# Microcontroller.net
KiCad netlist of a schematic drawn in Altium Designer
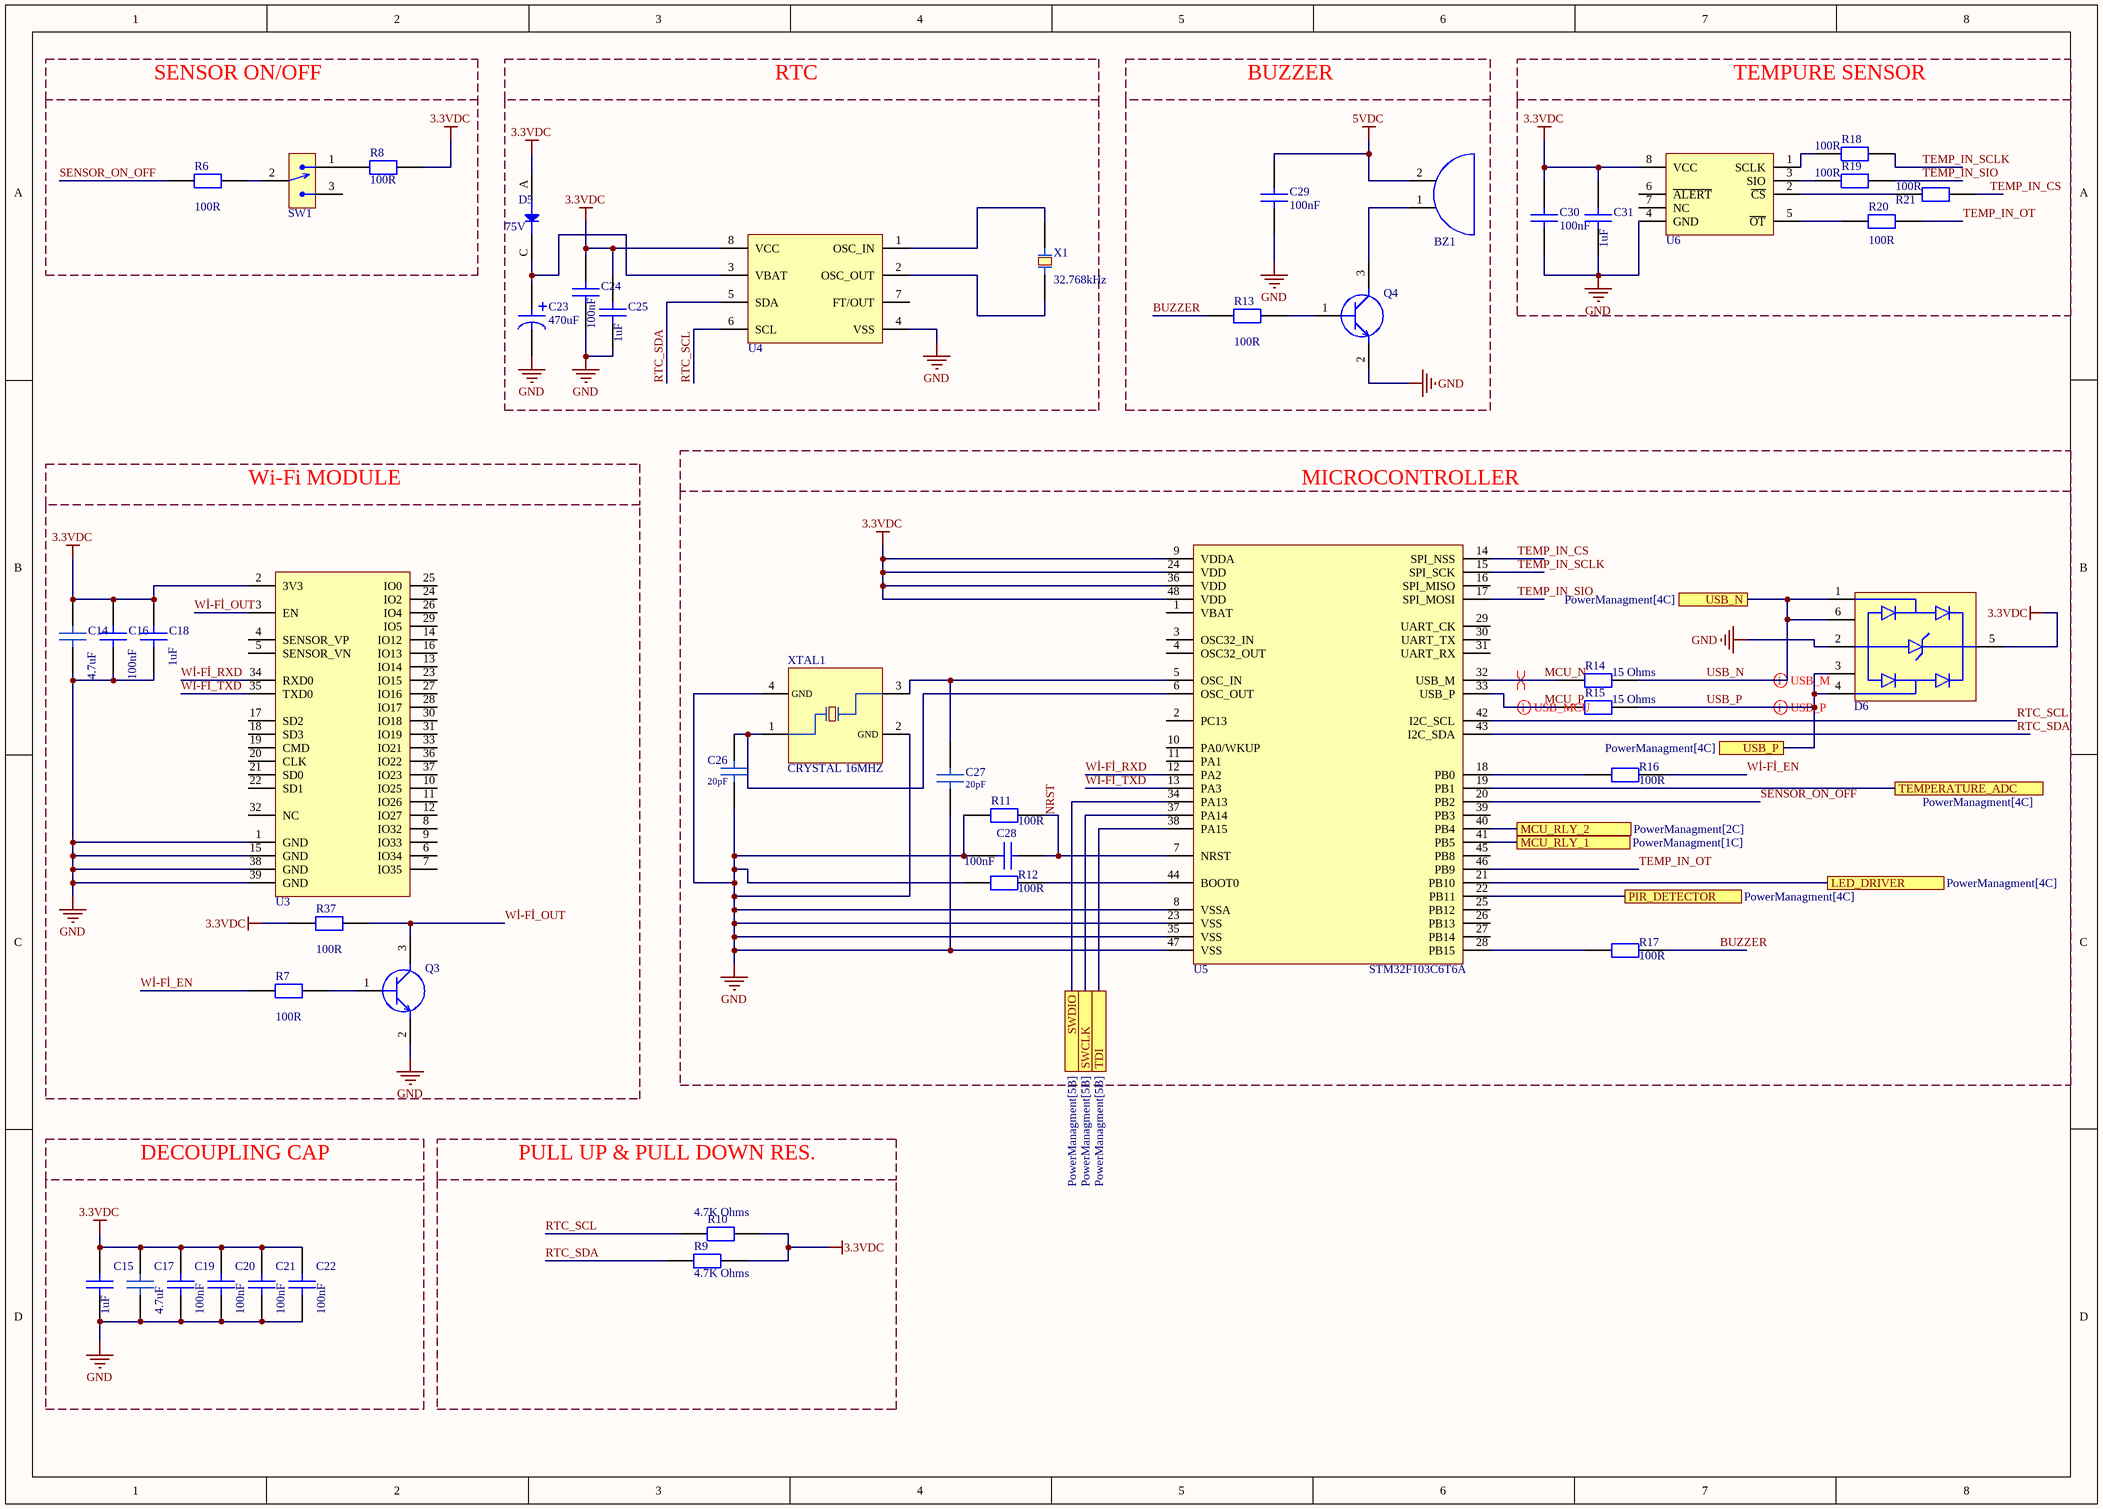
[diagram p0: Microcontroller.SchDoc]

(export (version "E")
  (design (tool "Eeschema 10.0.6"))
  (components
    (comp (ref "BZ1")
      (value "CMI-9605-0580T")
      (footprint "BUZZER CMI-9605-0580T")
      (description "9.6 mm, 5 Vdc, 80 dB, Through Hole, Driving Circuit, Magnetic Audio Indicator Buzzer")
      (fields (field (name "MANUFACTURER") "CUI Devices") (field (name "DESIGNED BY") "Görkem Bulut"))
      (libsource (lib "ComplexCurcuit") (part "CMI-9605-0580T"))
    )
    (comp (ref "C14")
      (value "4.7uF")
      (footprint "CAP 0805")
      (description "CAP CER 4.7UF 25V X5R 0805")
      (fields
        (field (name "MANUFACTURER") "Samsung")
        (field (name "MANUFACTURER PART NUMBER") "CL21A475KAQNNNE")
      )
      (libsource (lib "ComplexCurcuit") (part "CAP CER 4.7uF"))
    )
    (comp (ref "C15")
      (value "CAP CER 1UF 50V X7R 0805")
      (footprint "CAP 0805")
      (fields
        (field (name "MANUFACTURER") "Samsung")
        (field (name "MANUFACTURER PART NUMBER") "CL21B105KBFNNNE")
        (field (name "CAPACITANCE") "1uF")
        (field (name "DESIGNED BY") "Görkem Bulut")
      )
      (libsource (lib "ComplexCurcuit") (part "CAP CER 1uF"))
    )
    (comp (ref "C16")
      (value "CAP CER 100nF")
      (footprint "CAP 0603")
      (description "Cap Cer 0.1UF 16V X7R 0603 %10")
      (fields
        (field (name "MANUFACTURER") "KEMET")
        (field (name "MANUFACTURER PART NUMBER") "C0603C104K4RAC7082")
        (field (name "CAPACITANCE") "100nF")
        (field (name "DESIGNED BY") "Görkem Bulut")
      )
      (libsource (lib "ComplexCurcuit") (part "CAP CER 100nF"))
    )
    (comp (ref "C17")
      (value "4.7uF")
      (footprint "CAP 0805")
      (description "CAP CER 4.7UF 25V X5R 0805")
      (fields
        (field (name "MANUFACTURER") "Samsung")
        (field (name "MANUFACTURER PART NUMBER") "CL21A475KAQNNNE")
      )
      (libsource (lib "ComplexCurcuit") (part "CAP CER 4.7uF"))
    )
    (comp (ref "C18")
      (value "CAP CER 1UF 50V X7R 0805")
      (footprint "CAP 0805")
      (fields
        (field (name "MANUFACTURER") "Samsung")
        (field (name "MANUFACTURER PART NUMBER") "CL21B105KBFNNNE")
        (field (name "CAPACITANCE") "1uF")
        (field (name "DESIGNED BY") "Görkem Bulut")
      )
      (libsource (lib "ComplexCurcuit") (part "CAP CER 1uF"))
    )
    (comp (ref "C19")
      (value "CAP CER 100nF")
      (footprint "CAP 0603")
      (description "Cap Cer 0.1UF 16V X7R 0603 %10")
      (fields
        (field (name "MANUFACTURER") "KEMET")
        (field (name "MANUFACTURER PART NUMBER") "C0603C104K4RAC7082")
        (field (name "CAPACITANCE") "100nF")
        (field (name "DESIGNED BY") "Görkem Bulut")
      )
      (libsource (lib "ComplexCurcuit") (part "CAP CER 100nF"))
    )
    (comp (ref "C20")
      (value "CAP CER 100nF")
      (footprint "CAP 0603")
      (description "Cap Cer 0.1UF 16V X7R 0603 %10")
      (fields
        (field (name "MANUFACTURER") "KEMET")
        (field (name "MANUFACTURER PART NUMBER") "C0603C104K4RAC7082")
        (field (name "CAPACITANCE") "100nF")
        (field (name "DESIGNED BY") "Görkem Bulut")
      )
      (libsource (lib "ComplexCurcuit") (part "CAP CER 100nF"))
    )
    (comp (ref "C21")
      (value "CAP CER 100nF")
      (footprint "CAP 0603")
      (description "Cap Cer 0.1UF 16V X7R 0603 %10")
      (fields
        (field (name "MANUFACTURER") "KEMET")
        (field (name "MANUFACTURER PART NUMBER") "C0603C104K4RAC7082")
        (field (name "CAPACITANCE") "100nF")
        (field (name "DESIGNED BY") "Görkem Bulut")
      )
      (libsource (lib "ComplexCurcuit") (part "CAP CER 100nF"))
    )
    (comp (ref "C22")
      (value "CAP CER 100nF")
      (footprint "CAP 0603")
      (description "Cap Cer 0.1UF 16V X7R 0603 %10")
      (fields
        (field (name "MANUFACTURER") "KEMET")
        (field (name "MANUFACTURER PART NUMBER") "C0603C104K4RAC7082")
        (field (name "CAPACITANCE") "100nF")
        (field (name "DESIGNED BY") "Görkem Bulut")
      )
      (libsource (lib "ComplexCurcuit") (part "CAP CER 100nF"))
    )
    (comp (ref "C23")
      (value "ESH477M050AH4AA CAP")
      (footprint "CAP _RADİAL_D10_P5")
      (description "Cap, 470UF, 50V, Alu Elec, Radial")
      (fields
        (field (name "MANUFACTURER") "KEMET")
        (field (name "MANUFACTURER PART NUMBER") "ESH477M050AH4AA")
        (field (name "CAPACITANCE") "470uF")
        (field (name "DESIGNED BY") "Görkem Bulut")
      )
      (libsource (lib "ComplexCurcuit") (part "ESH477M050AH4AA CAP"))
    )
    (comp (ref "C24")
      (value "100nF")
      (footprint "CAP 0805")
      (description "Multilayer Ceramic Capacitor, 0.1 uF, 50 V, ± 10%, X7R, 0805 [2012 Metric]")
      (fields
        (field (name "MANUFACTURER") "Samsung")
        (field (name "MANUFACTURER PART NUMBER") "CL21B104KBCNNNC")
      )
      (libsource (lib "ComplexCurcuit") (part "CAP CER 100nF 0805"))
    )
    (comp (ref "C25")
      (value "CAP CER 1UF 50V X7R 0805")
      (footprint "CAP 0805")
      (fields
        (field (name "MANUFACTURER") "Samsung")
        (field (name "MANUFACTURER PART NUMBER") "CL21B105KBFNNNE")
        (field (name "CAPACITANCE") "1uF")
        (field (name "DESIGNED BY") "Görkem Bulut")
      )
      (libsource (lib "ComplexCurcuit") (part "CAP CER 1uF"))
    )
    (comp (ref "C26")
      (value "CAP CER 20PF 50V C0G/NP0 0603")
      (footprint "CAP 0603")
      (fields
        (field (name "MANUFACTURER") "Samsung")
        (field (name "MANUFACTURER PART NUMBER") "CL10C200JB8NNNC")
        (field (name "CAPACITANCE") "20pF")
      )
      (libsource (lib "ComplexCurcuit") (part "CAP CER 20pF"))
    )
    (comp (ref "C27")
      (value "CAP CER 20PF 50V C0G/NP0 0603")
      (footprint "CAP 0603")
      (fields
        (field (name "MANUFACTURER") "Samsung")
        (field (name "MANUFACTURER PART NUMBER") "CL10C200JB8NNNC")
        (field (name "CAPACITANCE") "20pF")
      )
      (libsource (lib "ComplexCurcuit") (part "CAP CER 20pF"))
    )
    (comp (ref "C28")
      (value "CAP CER 100nF")
      (footprint "CAP 0603")
      (description "Cap Cer 0.1UF 16V X7R 0603 %10")
      (fields
        (field (name "MANUFACTURER") "KEMET")
        (field (name "MANUFACTURER PART NUMBER") "C0603C104K4RAC7082")
        (field (name "CAPACITANCE") "100nF")
        (field (name "DESIGNED BY") "Görkem Bulut")
      )
      (libsource (lib "ComplexCurcuit") (part "CAP CER 100nF"))
    )
    (comp (ref "C29")
      (value "100nF")
      (footprint "CAP 0805")
      (description "Multilayer Ceramic Capacitor, 0.1 uF, 50 V, ± 10%, X7R, 0805 [2012 Metric]")
      (fields
        (field (name "MANUFACTURER") "Samsung")
        (field (name "MANUFACTURER PART NUMBER") "CL21B104KBCNNNC")
      )
      (libsource (lib "ComplexCurcuit") (part "CAP CER 100nF 0805"))
    )
    (comp (ref "C30")
      (value "CAP CER 100nF")
      (footprint "CAP 0603")
      (description "Cap Cer 0.1UF 16V X7R 0603 %10")
      (fields
        (field (name "MANUFACTURER") "KEMET")
        (field (name "MANUFACTURER PART NUMBER") "C0603C104K4RAC7082")
        (field (name "CAPACITANCE") "100nF")
        (field (name "DESIGNED BY") "Görkem Bulut")
      )
      (libsource (lib "ComplexCurcuit") (part "CAP CER 100nF"))
    )
    (comp (ref "C31")
      (value "CAP CER 1UF 50V X7R 0805")
      (footprint "CAP 0805")
      (fields
        (field (name "MANUFACTURER") "Samsung")
        (field (name "MANUFACTURER PART NUMBER") "CL21B105KBFNNNE")
        (field (name "CAPACITANCE") "1uF")
        (field (name "DESIGNED BY") "Görkem Bulut")
      )
      (libsource (lib "ComplexCurcuit") (part "CAP CER 1uF"))
    )
    (comp (ref "D5")
      (value "DIODE GEN PURP 75V 150MA SOD323F")
      (footprint "SOD323F")
      (description "VR=75V IF=150mA Trr=4ns P=200mW")
      (fields
        (field (name "MANUFACTURER") "ON Semiconductor / Fairchild")
        (field (name "MANUFACTURER PART NUMBER") "1N4148WS")
        (field (name "OPERATING VOLTAGE") "75V")
        (field (name "DESIGNED BY") "Görkem Bulut")
      )
      (libsource (lib "ComplexCurcuit") (part "1N4148WS"))
    )
    (comp (ref "D6")
      (value "TVS DIODE 5.25VWM 17VC SOT23-6")
      (footprint "SOT23-6L")
      (fields
        (field (name "MANUFACTURER") "STMicroelectronics")
        (field (name "MANUFACTURER PART NUMBER") "USBLC6-2SC6")
        (field (name "DESIGNED BY") "Görkem Bulut")
      )
      (libsource (lib "ComplexCurcuit") (part "USBLC6-2SC6"))
    )
    (comp (ref "Q3")
      (value "MMBT3904-7-F")
      (footprint "SOT23F")
      (description "Transistor General Purpose BJT NPN 40 Volt 0.2A Automotive 3-Pin SOT-23")
      (fields (field (name "MANUFACTURER") "Diodes Zetex") (field (name "DESIGNED BY") "Gökem Bulut"))
      (libsource (lib "ComplexCurcuit") (part "MMBT3904-7-F"))
    )
    (comp (ref "Q4")
      (value "MMBT3904-7-F")
      (footprint "SOT23F")
      (description "Transistor General Purpose BJT NPN 40 Volt 0.2A Automotive 3-Pin SOT-23")
      (fields (field (name "MANUFACTURER") "Diodes Zetex") (field (name "DESIGNED BY") "Gökem Bulut"))
      (libsource (lib "ComplexCurcuit") (part "MMBT3904-7-F"))
    )
    (comp (ref "R6")
      (value "RC0603JR-07100RL")
      (footprint "RES 0603")
      (description "Res Thick Film 0603 100 Ohm 5% 1/10W ±100ppm/°C Molded SMD SMD Paper T/R")
      (fields
        (field (name "MANUFACTURER") "Yageo")
        (field (name "TOLERANCE") "5%")
        (field (name "RESISTANCE") "100R")
        (field (name "DESIGNED BY") "G.B")
      )
      (libsource (lib "ComplexCurcuit") (part "RES 100 OHM"))
    )
    (comp (ref "R7")
      (value "RC0603JR-07100RL")
      (footprint "RES 0603")
      (description "Res Thick Film 0603 100 Ohm 5% 1/10W ±100ppm/°C Molded SMD SMD Paper T/R")
      (fields
        (field (name "MANUFACTURER") "Yageo")
        (field (name "TOLERANCE") "5%")
        (field (name "RESISTANCE") "100R")
        (field (name "DESIGNED BY") "G.B")
      )
      (libsource (lib "ComplexCurcuit") (part "RES 100 OHM"))
    )
    (comp (ref "R8")
      (value "RC0603JR-07100RL")
      (footprint "RES 0603")
      (description "Res Thick Film 0603 100 Ohm 5% 1/10W ±100ppm/°C Molded SMD SMD Paper T/R")
      (fields
        (field (name "MANUFACTURER") "Yageo")
        (field (name "TOLERANCE") "5%")
        (field (name "RESISTANCE") "100R")
        (field (name "DESIGNED BY") "G.B")
      )
      (libsource (lib "ComplexCurcuit") (part "RES 100 OHM"))
    )
    (comp (ref "R9")
      (value "RC0603JR-074K7L")
      (footprint "RES 0603")
      (description "Res General Purpose Thick Film 0603 4.7k Ohm 5% 1/10W ±100ppm/°C Molded Paper T/R")
      (fields
        (field (name "MANUFACTURER") "Yageo")
        (field (name "RESISTANCE") "4.7K Ohms")
        (field (name "DESIGNED BY") "Görkem Bulut")
      )
      (libsource (lib "ComplexCurcuit") (part "RES 4K7 OHM"))
    )
    (comp (ref "R10")
      (value "RC0603JR-074K7L")
      (footprint "RES 0603")
      (description "Res General Purpose Thick Film 0603 4.7k Ohm 5% 1/10W ±100ppm/°C Molded Paper T/R")
      (fields
        (field (name "MANUFACTURER") "Yageo")
        (field (name "RESISTANCE") "4.7K Ohms")
        (field (name "DESIGNED BY") "Görkem Bulut")
      )
      (libsource (lib "ComplexCurcuit") (part "RES 4K7 OHM"))
    )
    (comp (ref "R11")
      (value "RC0603JR-07100RL")
      (footprint "RES 0603")
      (description "Res Thick Film 0603 100 Ohm 5% 1/10W ±100ppm/°C Molded SMD SMD Paper T/R")
      (fields
        (field (name "MANUFACTURER") "Yageo")
        (field (name "TOLERANCE") "5%")
        (field (name "RESISTANCE") "100R")
        (field (name "DESIGNED BY") "G.B")
      )
      (libsource (lib "ComplexCurcuit") (part "RES 100 OHM"))
    )
    (comp (ref "R12")
      (value "RC0603JR-07100RL")
      (footprint "RES 0603")
      (description "Res Thick Film 0603 100 Ohm 5% 1/10W ±100ppm/°C Molded SMD SMD Paper T/R")
      (fields
        (field (name "MANUFACTURER") "Yageo")
        (field (name "TOLERANCE") "5%")
        (field (name "RESISTANCE") "100R")
        (field (name "DESIGNED BY") "G.B")
      )
      (libsource (lib "ComplexCurcuit") (part "RES 100 OHM"))
    )
    (comp (ref "R13")
      (value "RC0603JR-07100RL")
      (footprint "RES 0603")
      (description "Res Thick Film 0603 100 Ohm 5% 1/10W ±100ppm/°C Molded SMD SMD Paper T/R")
      (fields
        (field (name "MANUFACTURER") "Yageo")
        (field (name "TOLERANCE") "5%")
        (field (name "RESISTANCE") "100R")
        (field (name "DESIGNED BY") "G.B")
      )
      (libsource (lib "ComplexCurcuit") (part "RES 100 OHM"))
    )
    (comp (ref "R14")
      (value "RC0603JR-0715RL")
      (footprint "RES 0603")
      (description "Res Thick Film 0603 15 Ohm 5% 0.1W(1/10W) ±100ppm/C Pad SMD T/R")
      (fields
        (field (name "MANUFACTURER") "Yageo")
        (field (name "RESISTANCE") "15 Ohms")
        (field (name "DESIGNED BY") "Görkem Bulut")
      )
      (libsource (lib "ComplexCurcuit") (part "RES 15 OHM"))
    )
    (comp (ref "R15")
      (value "RC0603JR-0715RL")
      (footprint "RES 0603")
      (description "Res Thick Film 0603 15 Ohm 5% 0.1W(1/10W) ±100ppm/C Pad SMD T/R")
      (fields
        (field (name "MANUFACTURER") "Yageo")
        (field (name "RESISTANCE") "15 Ohms")
        (field (name "DESIGNED BY") "Görkem Bulut")
      )
      (libsource (lib "ComplexCurcuit") (part "RES 15 OHM"))
    )
    (comp (ref "R16")
      (value "RC0603JR-07100RL")
      (footprint "RES 0603")
      (description "Res Thick Film 0603 100 Ohm 5% 1/10W ±100ppm/°C Molded SMD SMD Paper T/R")
      (fields
        (field (name "MANUFACTURER") "Yageo")
        (field (name "TOLERANCE") "5%")
        (field (name "RESISTANCE") "100R")
        (field (name "DESIGNED BY") "G.B")
      )
      (libsource (lib "ComplexCurcuit") (part "RES 100 OHM"))
    )
    (comp (ref "R17")
      (value "RC0603JR-07100RL")
      (footprint "RES 0603")
      (description "Res Thick Film 0603 100 Ohm 5% 1/10W ±100ppm/°C Molded SMD SMD Paper T/R")
      (fields
        (field (name "MANUFACTURER") "Yageo")
        (field (name "TOLERANCE") "5%")
        (field (name "RESISTANCE") "100R")
        (field (name "DESIGNED BY") "G.B")
      )
      (libsource (lib "ComplexCurcuit") (part "RES 100 OHM"))
    )
    (comp (ref "R18")
      (value "RC0603JR-07100RL")
      (footprint "RES 0603")
      (description "Res Thick Film 0603 100 Ohm 5% 1/10W ±100ppm/°C Molded SMD SMD Paper T/R")
      (fields
        (field (name "MANUFACTURER") "Yageo")
        (field (name "TOLERANCE") "5%")
        (field (name "RESISTANCE") "100R")
        (field (name "DESIGNED BY") "G.B")
      )
      (libsource (lib "ComplexCurcuit") (part "RES 100 OHM"))
    )
    (comp (ref "R19")
      (value "RC0603JR-07100RL")
      (footprint "RES 0603")
      (description "Res Thick Film 0603 100 Ohm 5% 1/10W ±100ppm/°C Molded SMD SMD Paper T/R")
      (fields
        (field (name "MANUFACTURER") "Yageo")
        (field (name "TOLERANCE") "5%")
        (field (name "RESISTANCE") "100R")
        (field (name "DESIGNED BY") "G.B")
      )
      (libsource (lib "ComplexCurcuit") (part "RES 100 OHM"))
    )
    (comp (ref "R20")
      (value "RC0603JR-07100RL")
      (footprint "RES 0603")
      (description "Res Thick Film 0603 100 Ohm 5% 1/10W ±100ppm/°C Molded SMD SMD Paper T/R")
      (fields
        (field (name "MANUFACTURER") "Yageo")
        (field (name "TOLERANCE") "5%")
        (field (name "RESISTANCE") "100R")
        (field (name "DESIGNED BY") "G.B")
      )
      (libsource (lib "ComplexCurcuit") (part "RES 100 OHM"))
    )
    (comp (ref "R21")
      (value "RC0603JR-07100RL")
      (footprint "RES 0603")
      (description "Res Thick Film 0603 100 Ohm 5% 1/10W ±100ppm/°C Molded SMD SMD Paper T/R")
      (fields
        (field (name "MANUFACTURER") "Yageo")
        (field (name "TOLERANCE") "5%")
        (field (name "RESISTANCE") "100R")
        (field (name "DESIGNED BY") "G.B")
      )
      (libsource (lib "ComplexCurcuit") (part "RES 100 OHM"))
    )
    (comp (ref "R37")
      (value "RC0603JR-07100RL")
      (footprint "RES 0603")
      (description "Res Thick Film 0603 100 Ohm 5% 1/10W ±100ppm/°C Molded SMD SMD Paper T/R")
      (fields
        (field (name "MANUFACTURER") "Yageo")
        (field (name "TOLERANCE") "5%")
        (field (name "RESISTANCE") "100R")
        (field (name "DESIGNED BY") "G.B")
      )
      (libsource (lib "ComplexCurcuit") (part "RES 100 OHM"))
    )
    (comp (ref "SW1")
      (value "EG1215AA")
      (footprint "EG1215AA")
      (description "Slide Switch, SPDT, 0.025A, 24V, SMD")
      (fields (field (name "MANUFACTURER") "E-Switch") (field (name "DESIGNED BY") "Görkem Bulut"))
      (libsource (lib "ComplexCurcuit") (part "EG1215AA"))
    )
    (comp (ref "U3")
      (value "ESP32-VROOM-32")
      (footprint "ESP-32-32E")
      (fields
        (field (name "MANUFACTURER PART NUMBER") "ESP32-WROOM-32E(4MB)")
        (field (name "MANUFACTURER") "Espressif Systems")
        (field (name "DESIGNED BY") "Görkem Bulut")
      )
      (libsource (lib "ComplexCurcuit") (part "ESP32-VROOM-32"))
    )
    (comp (ref "U4")
      (value "M41T00M6F")
      (footprint "SOIC8")
      (description "Real-time Clocks Clock/Calendar I2C, 2-Wire Serial 70uA @ 2V ~ 5.5V SOIC-8_150mil RoHS")
      (fields (field (name "MANUFACTURER") "STMicroelectronics") (field (name "DESIGNED BY") "Görkem Bulut"))
      (libsource (lib "ComplexCurcuit") (part "M41T00M6F"))
    )
    (comp (ref "U5")
      (value "STM32F103C6T6A")
      (footprint "LQFP48")
      (description "MCU 32-bit STM32F ARM Cortex M3 RISC 32KB Flash 2.5V/3.3V 48-Pin LQFP Tray")
      (fields (field (name "MANUFACTURER") "STMicroelectronics") (field (name "DESIGNED BY") "Görkem BULUT"))
      (libsource (lib "ComplexCurcuit") (part "STM32F103C6T6A"))
    )
    (comp (ref "U6")
      (value "MAX6662MSA+")
      (footprint "SOIC8")
      (description "Temp Sensor Digital Serial (3-Wire, SPI) 8-Pin SOIC N Tube")
      (fields (field (name "MANUFACTURER") "Maxim") (field (name "DESIGNED BY") "Görkem Bulut"))
      (libsource (lib "ComplexCurcuit") (part "MAX6662MSA+"))
    )
    (comp (ref "X1")
      (value "CRYSTAL 32.7680KHZ 12.5PF SMD")
      (footprint "ABS05")
      (description "CRYSTAL 32.768kHz ±20ppm Crystal 12.5pF 90 kOhm -40°C ^ 85°C Surface Mount 2-SMD")
      (fields
        (field (name "MANUFACTURER") "Abracon")
        (field (name "MANUFACTURER PART NUMBER") "ABS05-32.768KHZ-T")
        (field (name "FREQUENCY") "32.768kHz")
      )
      (libsource (lib "ComplexCurcuit") (part "CRYSTAL OSC 32.768 kHz"))
    )
    (comp (ref "XTAL1")
      (value "CRYSTAL 16MHZ")
      (footprint "ECS-160-20-30B-TR")
      (description "Crystal 16MHz ±30ppm (Tol) ±50ppm (Stability) 20pF FUND 50Ohm 4-Pin Mini-SMD T/R")
      (fields
        (field (name "MANUFACTURER") "ECS International")
        (field (name "MANUFACTURER PART NUMBER") "ECS-160-20-30B-TR")
        (field (name "DESIGNED BY") "Görkem B.")
      )
      (libsource (lib "ComplexCurcuit") (part "CRYSTAL 16MHZ"))
    )
  )
  (nets
    (net (code "1") (name "/BUZZER") (class "Default")
      (node (ref "R13") (pin "1") (pinfunction "1_1") (pintype "passive"))
      (node (ref "R17") (pin "2") (pinfunction "2_2") (pintype "passive"))
    )
    (net (code "2") (name "/LED_DRIVER") (class "Default")
      (node (ref "U5") (pin "21") (pinfunction "PB10_21") (pintype "passive"))
    )
    (net (code "3") (name "/MCU_N") (class "Default")
      (node (ref "R14") (pin "2") (pinfunction "2_2") (pintype "passive"))
      (node (ref "U5") (pin "32") (pinfunction "_USB_M_32") (pintype "passive"))
    )
    (net (code "4") (name "/MCU_P") (class "Default")
      (node (ref "R15") (pin "2") (pinfunction "2_2") (pintype "passive"))
      (node (ref "U5") (pin "33") (pinfunction "_USB_P_33") (pintype "passive"))
    )
    (net (code "5") (name "/MCU_RLY_1") (class "Default")
      (node (ref "U5") (pin "41") (pinfunction "PB5_41") (pintype "passive"))
    )
    (net (code "6") (name "/MCU_RLY_2") (class "Default")
      (node (ref "U5") (pin "40") (pinfunction "PB4_40") (pintype "passive"))
    )
    (net (code "7") (name "/NRST") (class "Default")
      (node (ref "C28") (pin "2") (pinfunction "2_2") (pintype "passive"))
      (node (ref "R11") (pin "2") (pinfunction "2_2") (pintype "passive"))
      (node (ref "U5") (pin "7") (pinfunction "NRST_7") (pintype "passive"))
    )
    (net (code "8") (name "/PIR_DETECTOR") (class "Default")
      (node (ref "U5") (pin "22") (pinfunction "PB11_22") (pintype "passive"))
    )
    (net (code "9") (name "/RTC_SCL") (class "Default")
      (node (ref "R10") (pin "1") (pinfunction "1_1") (pintype "passive"))
      (node (ref "U4") (pin "6") (pinfunction "SCL_6") (pintype "passive"))
      (node (ref "U5") (pin "42") (pinfunction "I2C_SCL_42") (pintype "passive"))
    )
    (net (code "10") (name "/RTC_SDA") (class "Default")
      (node (ref "R9") (pin "1") (pinfunction "1_1") (pintype "passive"))
      (node (ref "U4") (pin "5") (pinfunction "SDA_5") (pintype "passive"))
      (node (ref "U5") (pin "43") (pinfunction "I2C_SDA_43") (pintype "passive"))
    )
    (net (code "11") (name "/SENSOR_ON_OFF") (class "Default")
      (node (ref "R6") (pin "1") (pinfunction "1_1") (pintype "passive"))
      (node (ref "U5") (pin "20") (pinfunction "PB2_20") (pintype "passive"))
    )
    (net (code "12") (name "/SWCLK") (class "Default")
      (node (ref "U5") (pin "37") (pinfunction "PA14_37") (pintype "passive"))
    )
    (net (code "13") (name "/SWDIO") (class "Default")
      (node (ref "U5") (pin "34") (pinfunction "PA13_34") (pintype "passive"))
    )
    (net (code "14") (name "/TDI") (class "Default")
      (node (ref "U5") (pin "38") (pinfunction "PA15_38") (pintype "passive"))
    )
    (net (code "15") (name "/TEMPERATURE_ADC") (class "Default")
      (node (ref "U5") (pin "19") (pinfunction "PB1_19") (pintype "passive"))
    )
    (net (code "16") (name "/TEMP_IN_CS") (class "Default")
      (node (ref "R21") (pin "2") (pinfunction "2_2") (pintype "passive"))
      (node (ref "U5") (pin "14") (pinfunction "SPI_NSS_14") (pintype "passive"))
    )
    (net (code "17") (name "/TEMP_IN_OT") (class "Default")
      (node (ref "R20") (pin "2") (pinfunction "2_2") (pintype "passive"))
      (node (ref "U5") (pin "46") (pinfunction "PB9_46") (pintype "passive"))
    )
    (net (code "18") (name "/TEMP_IN_SCLK") (class "Default")
      (node (ref "R18") (pin "2") (pinfunction "2_2") (pintype "passive"))
      (node (ref "U5") (pin "15") (pinfunction "SPI_SCK_15") (pintype "passive"))
    )
    (net (code "19") (name "/TEMP_IN_SIO") (class "Default")
      (node (ref "R19") (pin "2") (pinfunction "2_2") (pintype "passive"))
      (node (ref "U5") (pin "17") (pinfunction "SPI_MOSI_17") (pintype "passive"))
    )
    (net (code "20") (name "/USB_N") (class "Default")
      (node (ref "D6") (pin "1") (pinfunction "I/O1_1") (pintype "passive"))
      (node (ref "D6") (pin "6") (pinfunction "I/O1_6") (pintype "passive"))
      (node (ref "R14") (pin "1") (pinfunction "1_1") (pintype "passive"))
    )
    (net (code "21") (name "/USB_P") (class "Default")
      (node (ref "D6") (pin "3") (pinfunction "I/O2_3") (pintype "passive"))
      (node (ref "D6") (pin "4") (pinfunction "_I/O2_4") (pintype "passive"))
      (node (ref "R15") (pin "1") (pinfunction "1_1") (pintype "passive"))
    )
    (net (code "22") (name "/Wİ-Fİ_EN") (class "Default")
      (node (ref "R16") (pin "2") (pinfunction "2_2") (pintype "passive"))
      (node (ref "R7") (pin "1") (pinfunction "1_1") (pintype "passive"))
    )
    (net (code "23") (name "/Wİ-Fİ_OUT") (class "Default")
      (node (ref "Q3") (pin "3") (pinfunction "CONNECTOR_3") (pintype "passive"))
      (node (ref "R37") (pin "2") (pinfunction "2_2") (pintype "passive"))
      (node (ref "U3") (pin "3") (pinfunction "EN_3") (pintype "passive"))
    )
    (net (code "24") (name "/Wİ-Fİ_RXD") (class "Default")
      (node (ref "U3") (pin "34") (pinfunction "RXD0_34") (pintype "passive"))
      (node (ref "U5") (pin "12") (pinfunction "PA2_12") (pintype "passive"))
    )
    (net (code "25") (name "/Wİ-Fİ_TXD") (class "Default")
      (node (ref "U3") (pin "35") (pinfunction "TXD0_35") (pintype "passive"))
      (node (ref "U5") (pin "13") (pinfunction "PA3_13") (pintype "passive"))
    )
    (net (code "26") (name "3.3VDC") (class "Default")
      (node (ref "C14") (pin "2") (pinfunction "2_2") (pintype "passive"))
      (node (ref "C15") (pin "1") (pinfunction "1_1") (pintype "passive"))
      (node (ref "C16") (pin "2") (pinfunction "2_2") (pintype "passive"))
      (node (ref "C17") (pin "2") (pinfunction "2_2") (pintype "passive"))
      (node (ref "C18") (pin "1") (pinfunction "1_1") (pintype "passive"))
      (node (ref "C19") (pin "2") (pinfunction "2_2") (pintype "passive"))
      (node (ref "C20") (pin "2") (pinfunction "2_2") (pintype "passive"))
      (node (ref "C21") (pin "2") (pinfunction "2_2") (pintype "passive"))
      (node (ref "C22") (pin "2") (pinfunction "2_2") (pintype "passive"))
      (node (ref "C24") (pin "2") (pinfunction "2_2") (pintype "passive"))
      (node (ref "C25") (pin "1") (pinfunction "1_1") (pintype "passive"))
      (node (ref "C30") (pin "2") (pinfunction "2_2") (pintype "passive"))
      (node (ref "C31") (pin "1") (pinfunction "1_1") (pintype "passive"))
      (node (ref "D5") (pin "A") (pinfunction "Anode_A") (pintype "passive"))
      (node (ref "D6") (pin "5") (pinfunction "VBUS_5") (pintype "passive"))
      (node (ref "R10") (pin "2") (pinfunction "2_2") (pintype "passive"))
      (node (ref "R37") (pin "1") (pinfunction "1_1") (pintype "passive"))
      (node (ref "R8") (pin "2") (pinfunction "2_2") (pintype "passive"))
      (node (ref "R9") (pin "2") (pinfunction "2_2") (pintype "passive"))
      (node (ref "U3") (pin "2") (pinfunction "3V3_2") (pintype "passive"))
      (node (ref "U4") (pin "8") (pinfunction "VCC_8") (pintype "passive"))
      (node (ref "U5") (pin "24") (pinfunction "VDD_24") (pintype "passive"))
      (node (ref "U5") (pin "36") (pinfunction "VDD_36") (pintype "passive"))
      (node (ref "U5") (pin "48") (pinfunction "VDD_48") (pintype "passive"))
      (node (ref "U5") (pin "9") (pinfunction "VDDA_9") (pintype "passive"))
      (node (ref "U6") (pin "8") (pinfunction "VCC_8") (pintype "passive"))
    )
    (net (code "27") (name "5VDC") (class "Default")
      (node (ref "BZ1") (pin "2") (pinfunction "2_2") (pintype "passive"))
      (node (ref "C29") (pin "2") (pinfunction "2_2") (pintype "passive"))
    )
    (net (code "28") (name "GND") (class "Default")
      (node (ref "C14") (pin "1") (pinfunction "1_1") (pintype "passive"))
      (node (ref "C15") (pin "2") (pinfunction "2_2") (pintype "passive"))
      (node (ref "C16") (pin "1") (pinfunction "1_1") (pintype "passive"))
      (node (ref "C17") (pin "1") (pinfunction "1_1") (pintype "passive"))
      (node (ref "C18") (pin "2") (pinfunction "2_2") (pintype "passive"))
      (node (ref "C19") (pin "1") (pinfunction "1_1") (pintype "passive"))
      (node (ref "C20") (pin "1") (pinfunction "1_1") (pintype "passive"))
      (node (ref "C21") (pin "1") (pinfunction "1_1") (pintype "passive"))
      (node (ref "C22") (pin "1") (pinfunction "1_1") (pintype "passive"))
      (node (ref "C23") (pin "2") (pinfunction "2_2") (pintype "passive"))
      (node (ref "C24") (pin "1") (pinfunction "1_1") (pintype "passive"))
      (node (ref "C25") (pin "2") (pinfunction "2_2") (pintype "passive"))
      (node (ref "C26") (pin "1") (pinfunction "1_1") (pintype "passive"))
      (node (ref "C27") (pin "1") (pinfunction "1_1") (pintype "passive"))
      (node (ref "C28") (pin "1") (pinfunction "1_1") (pintype "passive"))
      (node (ref "C29") (pin "1") (pinfunction "1_1") (pintype "passive"))
      (node (ref "C30") (pin "1") (pinfunction "1_1") (pintype "passive"))
      (node (ref "C31") (pin "2") (pinfunction "2_2") (pintype "passive"))
      (node (ref "D6") (pin "2") (pinfunction "GND_2") (pintype "passive"))
      (node (ref "Q3") (pin "2") (pinfunction "EMİTTER_2") (pintype "passive"))
      (node (ref "Q4") (pin "2") (pinfunction "EMİTTER_2") (pintype "passive"))
      (node (ref "R11") (pin "1") (pinfunction "1_1") (pintype "passive"))
      (node (ref "R12") (pin "1") (pinfunction "1_1") (pintype "passive"))
      (node (ref "U3") (pin "1") (pinfunction "GND_1") (pintype "passive"))
      (node (ref "U3") (pin "15") (pinfunction "GND_15") (pintype "passive"))
      (node (ref "U3") (pin "38") (pinfunction "GND_38") (pintype "passive"))
      (node (ref "U3") (pin "39") (pinfunction "GND_39") (pintype "passive"))
      (node (ref "U4") (pin "4") (pinfunction "VSS_4") (pintype "passive"))
      (node (ref "U5") (pin "23") (pinfunction "VSS_23") (pintype "passive"))
      (node (ref "U5") (pin "35") (pinfunction "VSS_35") (pintype "passive"))
      (node (ref "U5") (pin "47") (pinfunction "VSS_47") (pintype "passive"))
      (node (ref "U5") (pin "8") (pinfunction "VSSA_8") (pintype "passive"))
      (node (ref "U6") (pin "4") (pinfunction "GND_4") (pintype "passive"))
      (node (ref "XTAL1") (pin "2") (pinfunction "GND_2") (pintype "passive"))
      (node (ref "XTAL1") (pin "4") (pinfunction "GND_4") (pintype "passive"))
    )
    (net (code "29") (name "Net-(D5-Cathode)") (class "Default")
      (node (ref "C23") (pin "1") (pinfunction "1_1") (pintype "passive"))
      (node (ref "D5") (pin "C") (pinfunction "Cathode_C") (pintype "passive"))
      (node (ref "U4") (pin "3") (pinfunction "VBAT_3") (pintype "passive"))
    )
    (net (code "30") (name "Net-(Q3-BASE)") (class "Default")
      (node (ref "Q3") (pin "1") (pinfunction "BASE_1") (pintype "passive"))
      (node (ref "R7") (pin "2") (pinfunction "2_2") (pintype "passive"))
    )
    (net (code "31") (name "Net-(Q4-BASE)") (class "Default")
      (node (ref "Q4") (pin "1") (pinfunction "BASE_1") (pintype "passive"))
      (node (ref "R13") (pin "2") (pinfunction "2_2") (pintype "passive"))
    )
    (net (code "32") (name "Net-(Q4-CONNECTOR)") (class "Default")
      (node (ref "BZ1") (pin "1") (pinfunction "1_1") (pintype "passive"))
      (node (ref "Q4") (pin "3") (pinfunction "CONNECTOR_3") (pintype "passive"))
    )
    (net (code "33") (name "Net-(R6-Pad2)") (class "Default")
      (node (ref "R6") (pin "2") (pinfunction "2_2") (pintype "passive"))
      (node (ref "SW1") (pin "2") (pinfunction "2_2") (pintype "passive"))
    )
    (net (code "34") (name "Net-(R8-Pad1)") (class "Default")
      (node (ref "R8") (pin "1") (pinfunction "1_1") (pintype "passive"))
      (node (ref "SW1") (pin "1") (pinfunction "1_1") (pintype "passive"))
    )
    (net (code "35") (name "Net-(U4-OSC_IN)") (class "Default")
      (node (ref "U4") (pin "1") (pinfunction "OSC_IN_1") (pintype "passive"))
      (node (ref "X1") (pin "1") (pinfunction "1_1") (pintype "passive"))
    )
    (net (code "36") (name "Net-(U4-OSC_OUT)") (class "Default")
      (node (ref "U4") (pin "2") (pinfunction "OSC_OUT_2") (pintype "passive"))
      (node (ref "X1") (pin "2") (pinfunction "2_2") (pintype "passive"))
    )
    (net (code "37") (name "Net-(U5-BOOT0)") (class "Default")
      (node (ref "R12") (pin "2") (pinfunction "2_2") (pintype "passive"))
      (node (ref "U5") (pin "44") (pinfunction "BOOT0_44") (pintype "passive"))
    )
    (net (code "38") (name "Net-(U5-OSC_IN)") (class "Default")
      (node (ref "C27") (pin "2") (pinfunction "2_2") (pintype "passive"))
      (node (ref "U5") (pin "5") (pinfunction "OSC_IN_5") (pintype "passive"))
      (node (ref "XTAL1") (pin "3") (pinfunction "OUT/IN_3") (pintype "passive"))
    )
    (net (code "39") (name "Net-(U5-OSC_OUT)") (class "Default")
      (node (ref "C26") (pin "2") (pinfunction "2_2") (pintype "passive"))
      (node (ref "U5") (pin "6") (pinfunction "OSC_OUT_6") (pintype "passive"))
      (node (ref "XTAL1") (pin "1") (pinfunction "IN/OUT_1") (pintype "passive"))
    )
    (net (code "40") (name "Net-(U5-PB0)") (class "Default")
      (node (ref "R16") (pin "1") (pinfunction "1_1") (pintype "passive"))
      (node (ref "U5") (pin "18") (pinfunction "PB0_18") (pintype "passive"))
    )
    (net (code "41") (name "Net-(U5-PB15)") (class "Default")
      (node (ref "R17") (pin "1") (pinfunction "1_1") (pintype "passive"))
      (node (ref "U5") (pin "28") (pinfunction "PB15_28") (pintype "passive"))
    )
    (net (code "42") (name "Net-(U6-SCLK)") (class "Default")
      (node (ref "R18") (pin "1") (pinfunction "1_1") (pintype "passive"))
      (node (ref "U6") (pin "1") (pinfunction "SCLK_1") (pintype "passive"))
    )
    (net (code "43") (name "Net-(U6-SIO)") (class "Default")
      (node (ref "R19") (pin "1") (pinfunction "1_1") (pintype "passive"))
      (node (ref "U6") (pin "3") (pinfunction "SIO_3") (pintype "passive"))
    )
    (net (code "44") (name "Net-(U6-~{CS})") (class "Default")
      (node (ref "R21") (pin "1") (pinfunction "1_1") (pintype "passive"))
      (node (ref "U6") (pin "2") (pinfunction "~{CS}_2") (pintype "passive"))
    )
    (net (code "45") (name "Net-(U6-~{OT})") (class "Default")
      (node (ref "R20") (pin "1") (pinfunction "1_1") (pintype "passive"))
      (node (ref "U6") (pin "5") (pinfunction "~{OT}_5") (pintype "passive"))
    )
    (net (code "46") (name "unconnected-(SW1-Pad3)") (class "Default")
      (node (ref "SW1") (pin "3") (pinfunction "3_3") (pintype "passive"))
    )
    (net (code "47") (name "unconnected-(U3-CLK-Pad20)") (class "Default")
      (node (ref "U3") (pin "20") (pinfunction "CLK_20") (pintype "passive"))
    )
    (net (code "48") (name "unconnected-(U3-CMD-Pad19)") (class "Default")
      (node (ref "U3") (pin "19") (pinfunction "CMD_19") (pintype "passive"))
    )
    (net (code "49") (name "unconnected-(U3-IO0-Pad25)") (class "Default")
      (node (ref "U3") (pin "25") (pinfunction "IO0_25") (pintype "passive"))
    )
    (net (code "50") (name "unconnected-(U3-IO2-Pad24)") (class "Default")
      (node (ref "U3") (pin "24") (pinfunction "IO2_24") (pintype "passive"))
    )
    (net (code "51") (name "unconnected-(U3-IO4-Pad26)") (class "Default")
      (node (ref "U3") (pin "26") (pinfunction "IO4_26") (pintype "passive"))
    )
    (net (code "52") (name "unconnected-(U3-IO5-Pad29)") (class "Default")
      (node (ref "U3") (pin "29") (pinfunction "IO5_29") (pintype "passive"))
    )
    (net (code "53") (name "unconnected-(U3-IO12-Pad14)") (class "Default")
      (node (ref "U3") (pin "14") (pinfunction "IO12_14") (pintype "passive"))
    )
    (net (code "54") (name "unconnected-(U3-IO13-Pad16)") (class "Default")
      (node (ref "U3") (pin "16") (pinfunction "IO13_16") (pintype "passive"))
    )
    (net (code "55") (name "unconnected-(U3-IO14-Pad13)") (class "Default")
      (node (ref "U3") (pin "13") (pinfunction "IO14_13") (pintype "passive"))
    )
    (net (code "56") (name "unconnected-(U3-IO15-Pad23)") (class "Default")
      (node (ref "U3") (pin "23") (pinfunction "IO15_23") (pintype "passive"))
    )
    (net (code "57") (name "unconnected-(U3-IO16-Pad27)") (class "Default")
      (node (ref "U3") (pin "27") (pinfunction "IO16_27") (pintype "passive"))
    )
    (net (code "58") (name "unconnected-(U3-IO17-Pad28)") (class "Default")
      (node (ref "U3") (pin "28") (pinfunction "IO17_28") (pintype "passive"))
    )
    (net (code "59") (name "unconnected-(U3-IO18-Pad30)") (class "Default")
      (node (ref "U3") (pin "30") (pinfunction "IO18_30") (pintype "passive"))
    )
    (net (code "60") (name "unconnected-(U3-IO19-Pad31)") (class "Default")
      (node (ref "U3") (pin "31") (pinfunction "IO19_31") (pintype "passive"))
    )
    (net (code "61") (name "unconnected-(U3-IO21-Pad33)") (class "Default")
      (node (ref "U3") (pin "33") (pinfunction "IO21_33") (pintype "passive"))
    )
    (net (code "62") (name "unconnected-(U3-IO22-Pad36)") (class "Default")
      (node (ref "U3") (pin "36") (pinfunction "IO22_36") (pintype "passive"))
    )
    (net (code "63") (name "unconnected-(U3-IO23-Pad37)") (class "Default")
      (node (ref "U3") (pin "37") (pinfunction "IO23_37") (pintype "passive"))
    )
    (net (code "64") (name "unconnected-(U3-IO25-Pad10)") (class "Default")
      (node (ref "U3") (pin "10") (pinfunction "IO25_10") (pintype "passive"))
    )
    (net (code "65") (name "unconnected-(U3-IO26-Pad11)") (class "Default")
      (node (ref "U3") (pin "11") (pinfunction "IO26_11") (pintype "passive"))
    )
    (net (code "66") (name "unconnected-(U3-IO27-Pad12)") (class "Default")
      (node (ref "U3") (pin "12") (pinfunction "IO27_12") (pintype "passive"))
    )
    (net (code "67") (name "unconnected-(U3-IO32-Pad8)") (class "Default")
      (node (ref "U3") (pin "8") (pinfunction "IO32_8") (pintype "passive"))
    )
    (net (code "68") (name "unconnected-(U3-IO33-Pad9)") (class "Default")
      (node (ref "U3") (pin "9") (pinfunction "IO33_9") (pintype "passive"))
    )
    (net (code "69") (name "unconnected-(U3-IO34-Pad6)") (class "Default")
      (node (ref "U3") (pin "6") (pinfunction "IO34_6") (pintype "passive"))
    )
    (net (code "70") (name "unconnected-(U3-IO35-Pad7)") (class "Default")
      (node (ref "U3") (pin "7") (pinfunction "IO35_7") (pintype "passive"))
    )
    (net (code "71") (name "unconnected-(U3-NC-Pad32)") (class "Default")
      (node (ref "U3") (pin "32") (pinfunction "NC_32") (pintype "passive"))
    )
    (net (code "72") (name "unconnected-(U3-SD0-Pad21)") (class "Default")
      (node (ref "U3") (pin "21") (pinfunction "SD0_21") (pintype "passive"))
    )
    (net (code "73") (name "unconnected-(U3-SD1-Pad22)") (class "Default")
      (node (ref "U3") (pin "22") (pinfunction "SD1_22") (pintype "passive"))
    )
    (net (code "74") (name "unconnected-(U3-SD2-Pad17)") (class "Default")
      (node (ref "U3") (pin "17") (pinfunction "SD2_17") (pintype "passive"))
    )
    (net (code "75") (name "unconnected-(U3-SD3-Pad18)") (class "Default")
      (node (ref "U3") (pin "18") (pinfunction "SD3_18") (pintype "passive"))
    )
    (net (code "76") (name "unconnected-(U3-SENSOR_VN-Pad5)") (class "Default")
      (node (ref "U3") (pin "5") (pinfunction "SENSOR_VN_5") (pintype "passive"))
    )
    (net (code "77") (name "unconnected-(U3-SENSOR_VP-Pad4)") (class "Default")
      (node (ref "U3") (pin "4") (pinfunction "SENSOR_VP_4") (pintype "passive"))
    )
    (net (code "78") (name "unconnected-(U4-FT{slash}OUT-Pad7)") (class "Default")
      (node (ref "U4") (pin "7") (pinfunction "FT/OUT_7") (pintype "passive"))
    )
    (net (code "79") (name "unconnected-(U5-OSC32_IN-Pad3)") (class "Default")
      (node (ref "U5") (pin "3") (pinfunction "OSC32_IN_3") (pintype "passive"))
    )
    (net (code "80") (name "unconnected-(U5-OSC32_OUT-Pad4)") (class "Default")
      (node (ref "U5") (pin "4") (pinfunction "OSC32_OUT_4") (pintype "passive"))
    )
    (net (code "81") (name "unconnected-(U5-PA0{slash}WKUP-Pad10)") (class "Default")
      (node (ref "U5") (pin "10") (pinfunction "PA0/WKUP_10") (pintype "passive"))
    )
    (net (code "82") (name "unconnected-(U5-PA1-Pad11)") (class "Default")
      (node (ref "U5") (pin "11") (pinfunction "PA1_11") (pintype "passive"))
    )
    (net (code "83") (name "unconnected-(U5-PB3-Pad39)") (class "Default")
      (node (ref "U5") (pin "39") (pinfunction "PB3_39") (pintype "passive"))
    )
    (net (code "84") (name "unconnected-(U5-PB8-Pad45)") (class "Default")
      (node (ref "U5") (pin "45") (pinfunction "PB8_45") (pintype "passive"))
    )
    (net (code "85") (name "unconnected-(U5-PB12-Pad25)") (class "Default")
      (node (ref "U5") (pin "25") (pinfunction "PB12_25") (pintype "passive"))
    )
    (net (code "86") (name "unconnected-(U5-PB13-Pad26)") (class "Default")
      (node (ref "U5") (pin "26") (pinfunction "PB13_26") (pintype "passive"))
    )
    (net (code "87") (name "unconnected-(U5-PB14-Pad27)") (class "Default")
      (node (ref "U5") (pin "27") (pinfunction "PB14_27") (pintype "passive"))
    )
    (net (code "88") (name "unconnected-(U5-PC13-Pad2)") (class "Default")
      (node (ref "U5") (pin "2") (pinfunction "PC13_2") (pintype "passive"))
    )
    (net (code "89") (name "unconnected-(U5-SPI_MISO-Pad16)") (class "Default")
      (node (ref "U5") (pin "16") (pinfunction "SPI_MISO_16") (pintype "passive"))
    )
    (net (code "90") (name "unconnected-(U5-UART_CK-Pad29)") (class "Default")
      (node (ref "U5") (pin "29") (pinfunction "UART_CK_29") (pintype "passive"))
    )
    (net (code "91") (name "unconnected-(U5-UART_RX-Pad31)") (class "Default")
      (node (ref "U5") (pin "31") (pinfunction "UART_RX_31") (pintype "passive"))
    )
    (net (code "92") (name "unconnected-(U5-UART_TX-Pad30)") (class "Default")
      (node (ref "U5") (pin "30") (pinfunction "UART_TX_30") (pintype "passive"))
    )
    (net (code "93") (name "unconnected-(U5-VBAT-Pad1)") (class "Default")
      (node (ref "U5") (pin "1") (pinfunction "VBAT_1") (pintype "passive"))
    )
    (net (code "94") (name "unconnected-(U6-NC-Pad7)") (class "Default")
      (node (ref "U6") (pin "7") (pinfunction "NC_7") (pintype "passive"))
    )
    (net (code "95") (name "unconnected-(U6-~{ALERT}-Pad6)") (class "Default")
      (node (ref "U6") (pin "6") (pinfunction "~{ALERT}_6") (pintype "passive"))
    )
  )
)
